# MCUPro.net
KiCad netlist of a schematic drawn in Altium Designer
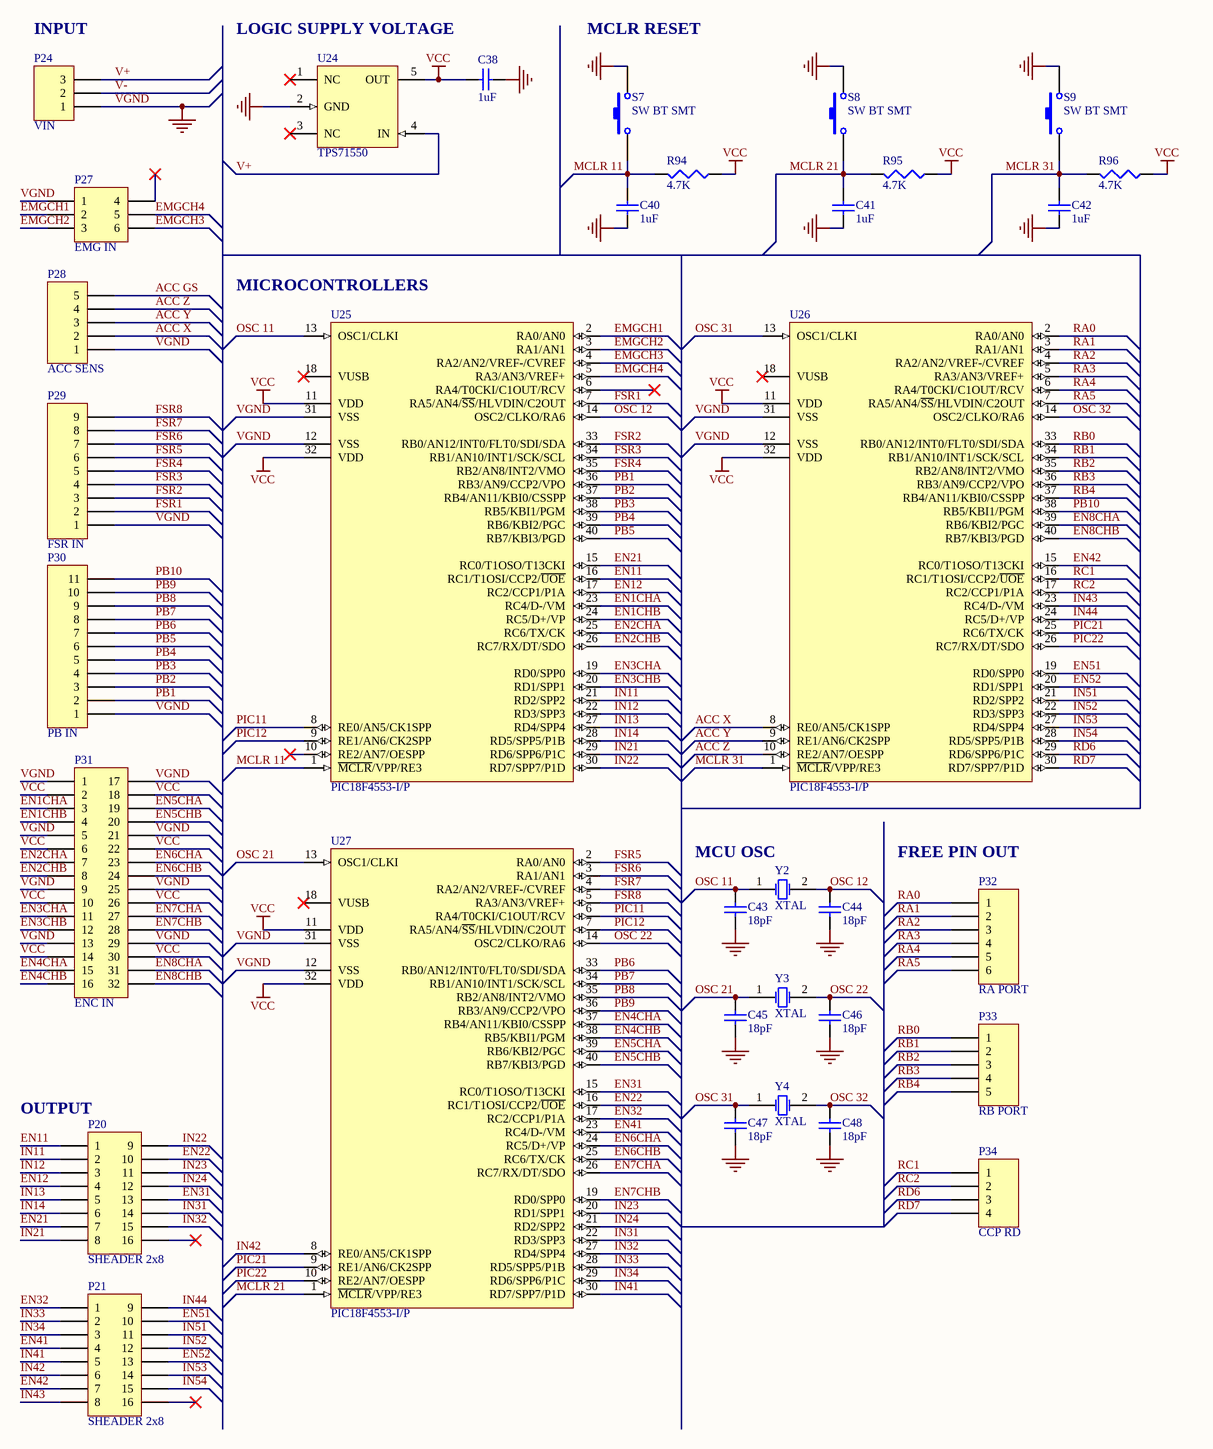
[diagram p0: MCUPro.SchDoc]

(export (version "E")
  (design (tool "Eeschema 10.0.6"))
  (components
    (comp (ref "C38")
      (value "1uF")
      (footprint "CAPC2012M")
      (description "Capacitor (Semiconductor SIM Model)")
      (fields (field (name "Comment") "Cap Semi") (field (name "PUBLISHER") "Altium Limited"))
      (libsource (lib "Miscellaneous Devices") (part "Cap Semi"))
    )
    (comp (ref "C40")
      (value "1uF")
      (footprint "CAPC2012M")
      (description "Capacitor (Semiconductor SIM Model)")
      (fields (field (name "Comment") "Cap Semi") (field (name "PUBLISHER") "Altium Limited"))
      (libsource (lib "Miscellaneous Devices") (part "Cap Semi"))
    )
    (comp (ref "C41")
      (value "1uF")
      (footprint "CAPC2012M")
      (description "Capacitor (Semiconductor SIM Model)")
      (fields (field (name "Comment") "Cap Semi") (field (name "PUBLISHER") "Altium Limited"))
      (libsource (lib "Miscellaneous Devices") (part "Cap Semi"))
    )
    (comp (ref "C42")
      (value "1uF")
      (footprint "CAPC2012M")
      (description "Capacitor (Semiconductor SIM Model)")
      (fields (field (name "Comment") "Cap Semi") (field (name "PUBLISHER") "Altium Limited"))
      (libsource (lib "Miscellaneous Devices") (part "Cap Semi"))
    )
    (comp (ref "C43")
      (value "18pF")
      (footprint "C1206")
      (description "Capacitor (Semiconductor SIM Model)")
      (fields (field (name "Comment") "Cap Semi") (field (name "PUBLISHER") "Altium Limited"))
      (libsource (lib "Miscellaneous Devices") (part "Cap Semi"))
    )
    (comp (ref "C44")
      (value "18pF")
      (footprint "C1206")
      (description "Capacitor (Semiconductor SIM Model)")
      (fields (field (name "Comment") "Cap Semi") (field (name "PUBLISHER") "Altium Limited"))
      (libsource (lib "Miscellaneous Devices") (part "Cap Semi"))
    )
    (comp (ref "C45")
      (value "18pF")
      (footprint "C1206")
      (description "Capacitor (Semiconductor SIM Model)")
      (fields (field (name "Comment") "Cap Semi") (field (name "PUBLISHER") "Altium Limited"))
      (libsource (lib "Miscellaneous Devices") (part "Cap Semi"))
    )
    (comp (ref "C46")
      (value "18pF")
      (footprint "C1206")
      (description "Capacitor (Semiconductor SIM Model)")
      (fields (field (name "Comment") "Cap Semi") (field (name "PUBLISHER") "Altium Limited"))
      (libsource (lib "Miscellaneous Devices") (part "Cap Semi"))
    )
    (comp (ref "C47")
      (value "18pF")
      (footprint "C1206")
      (description "Capacitor (Semiconductor SIM Model)")
      (fields (field (name "Comment") "Cap Semi") (field (name "PUBLISHER") "Altium Limited"))
      (libsource (lib "Miscellaneous Devices") (part "Cap Semi"))
    )
    (comp (ref "C48")
      (value "18pF")
      (footprint "C1206")
      (description "Capacitor (Semiconductor SIM Model)")
      (fields (field (name "Comment") "Cap Semi") (field (name "PUBLISHER") "Altium Limited"))
      (libsource (lib "Miscellaneous Devices") (part "Cap Semi"))
    )
    (comp (ref "P20")
      (value "SHEADER 2x8")
      (footprint "SHBH 2X8")
      (description "Shrouded Box Header: 2x8-Pin, 0.100\" (2.54 mm) Male")
      (libsource (lib "LitoLibrary") (part "SB Header 2x8"))
    )
    (comp (ref "P21")
      (value "SHEADER 2x8")
      (footprint "SHBH 2X8")
      (description "Shrouded Box Header: 2x8-Pin, 0.100\" (2.54 mm) Male")
      (libsource (lib "LitoLibrary") (part "SB Header 2x8"))
    )
    (comp (ref "P24")
      (value "VIN")
      (footprint "AZUL5-3")
      (description "Header, 3-Pin")
      (fields (field (name "PUBLISHER") "Altium Limited"))
      (libsource (lib "Miscellaneous Connectors") (part "Header 3"))
    )
    (comp (ref "P27")
      (value "EMG IN")
      (footprint "SHBH 2x3")
      (description "Shrouded Box Header: 2x8-Pin, 0.100\" (2.54 mm) Male")
      (libsource (lib "LitoLibrary") (part "SB Header 2x3"))
    )
    (comp (ref "P28")
      (value "ACC SENS")
      (footprint "HDR1X5H")
      (description "Header, 5-Pin, Right Angle")
      (fields (field (name "PUBLISHER") "Altium Limited"))
      (libsource (lib "Miscellaneous Connectors") (part "Header 5H"))
    )
    (comp (ref "P29")
      (value "FSR IN")
      (footprint "HDR1X9H")
      (description "Header, 9-Pin, Right Angle")
      (fields (field (name "PUBLISHER") "Altium Limited"))
      (libsource (lib "Miscellaneous Connectors") (part "Header 9H"))
    )
    (comp (ref "P30")
      (value "PB IN")
      (footprint "HDR1X11H")
      (description "Header, 11-Pin, Right Angle")
      (fields (field (name "PUBLISHER") "Altium Limited"))
      (libsource (lib "Miscellaneous Connectors") (part "Header 11H"))
    )
    (comp (ref "P31")
      (value "ENC IN")
      (footprint "HDR2X16_CEN")
      (description "Header, 16-Pin, Dual row")
      (fields (field (name "PUBLISHER") "Altium Limited"))
      (libsource (lib "Miscellaneous Connectors") (part "Header 16X2A"))
    )
    (comp (ref "P32")
      (value "RA PORT")
      (footprint "AZUL5-6")
      (description "Header, 6-Pin")
      (fields (field (name "PUBLISHER") "Altium Limited"))
      (libsource (lib "Miscellaneous Connectors") (part "Header 6"))
    )
    (comp (ref "P33")
      (value "RB PORT")
      (footprint "HDR1X5")
      (description "Header, 5-Pin")
      (fields (field (name "PUBLISHER") "Altium Limited"))
      (libsource (lib "Miscellaneous Connectors") (part "Header 5"))
    )
    (comp (ref "P34")
      (value "CCP RD")
      (footprint "HDR1X4")
      (description "Header, 4-Pin")
      (fields (field (name "PUBLISHER") "Altium Limited"))
      (libsource (lib "Miscellaneous Connectors") (part "Header 4"))
    )
    (comp (ref "R94")
      (value "4.7K")
      (footprint "RESC3225M")
      (description "Resistor")
      (fields (field (name "Comment") "Res3") (field (name "PUBLISHER") "Altium Limited"))
      (libsource (lib "Miscellaneous Devices") (part "Res3"))
    )
    (comp (ref "R95")
      (value "4.7K")
      (footprint "RESC3225M")
      (description "Resistor")
      (fields (field (name "Comment") "Res3") (field (name "PUBLISHER") "Altium Limited"))
      (libsource (lib "Miscellaneous Devices") (part "Res3"))
    )
    (comp (ref "R96")
      (value "4.7K")
      (footprint "RESC3225M")
      (description "Resistor")
      (fields (field (name "Comment") "Res3") (field (name "PUBLISHER") "Altium Limited"))
      (libsource (lib "Miscellaneous Devices") (part "Res3"))
    )
    (comp (ref "S7")
      (value "SW BT SMT")
      (footprint "PBOTTON SMT4")
      (description "Pushbutton Switches FSM2JSMAASTR=6MM TACT SWITCH,")
      (libsource (lib "LitoLibrary") (part "SW PB 6mm"))
    )
    (comp (ref "S8")
      (value "SW BT SMT")
      (footprint "PBOTTON SMT4")
      (description "Pushbutton Switches FSM2JSMAASTR=6MM TACT SWITCH,")
      (libsource (lib "LitoLibrary") (part "SW PB 6mm"))
    )
    (comp (ref "S9")
      (value "SW BT SMT")
      (footprint "PBOTTON SMT4")
      (description "Pushbutton Switches FSM2JSMAASTR=6MM TACT SWITCH,")
      (libsource (lib "LitoLibrary") (part "SW PB 6mm"))
    )
    (comp (ref "U24")
      (value "TPS71550")
      (footprint "SOT353-5L")
      (libsource (lib "LitoLibrary") (part "TPS71550"))
    )
    (comp (ref "U25")
      (value "PIC18F4553-I/P")
      (footprint "PDIP600-P40")
      (fields (field (name "PUBLISHER") "Altium Limited"))
      (libsource (lib "Microchip Microcontroller 8-Bit PIC18") (part "PIC18F4553-I/P"))
    )
    (comp (ref "U26")
      (value "PIC18F4553-I/P")
      (footprint "PDIP600-P40")
      (fields (field (name "PUBLISHER") "Altium Limited"))
      (libsource (lib "Microchip Microcontroller 8-Bit PIC18") (part "PIC18F4553-I/P"))
    )
    (comp (ref "U27")
      (value "PIC18F4553-I/P")
      (footprint "PDIP600-P40")
      (fields (field (name "PUBLISHER") "Altium Limited"))
      (libsource (lib "Microchip Microcontroller 8-Bit PIC18") (part "PIC18F4553-I/P"))
    )
    (comp (ref "Y2")
      (value "XTAL")
      (footprint "XTAL-1")
      (description "Crystal Oscillator")
      (fields (field (name "PUBLISHER") "Altium Limited"))
      (libsource (lib "Miscellaneous Devices") (part "XTAL"))
    )
    (comp (ref "Y3")
      (value "XTAL")
      (footprint "XTAL-1")
      (description "Crystal Oscillator")
      (fields (field (name "PUBLISHER") "Altium Limited"))
      (libsource (lib "Miscellaneous Devices") (part "XTAL"))
    )
    (comp (ref "Y4")
      (value "XTAL")
      (footprint "XTAL-1")
      (description "Crystal Oscillator")
      (fields (field (name "PUBLISHER") "Altium Limited"))
      (libsource (lib "Miscellaneous Devices") (part "XTAL"))
    )
  )
  (nets
    (net (code "1") (name "/ACC GS") (class "Default")
      (node (ref "P28") (pin "5") (pinfunction "5_5") (pintype "passive"))
    )
    (net (code "2") (name "/ACC X") (class "Default")
      (node (ref "P28") (pin "2") (pinfunction "2_2") (pintype "passive"))
      (node (ref "U26") (pin "8") (pinfunction "RE0/AN5/CK1SPP_8") (pintype "bidirectional"))
    )
    (net (code "3") (name "/ACC Y") (class "Default")
      (node (ref "P28") (pin "3") (pinfunction "3_3") (pintype "passive"))
      (node (ref "U26") (pin "9") (pinfunction "RE1/AN6/CK2SPP_9") (pintype "bidirectional"))
    )
    (net (code "4") (name "/ACC Z") (class "Default")
      (node (ref "P28") (pin "4") (pinfunction "4_4") (pintype "passive"))
      (node (ref "U26") (pin "10") (pinfunction "RE2/AN7/OESPP_10") (pintype "bidirectional"))
    )
    (net (code "5") (name "/EMGCH1") (class "Default")
      (node (ref "P27") (pin "2") (pinfunction "2_2") (pintype "passive"))
      (node (ref "U25") (pin "2") (pinfunction "RA0/AN0_2") (pintype "bidirectional"))
    )
    (net (code "6") (name "/EMGCH2") (class "Default")
      (node (ref "P27") (pin "3") (pinfunction "3_3") (pintype "passive"))
      (node (ref "U25") (pin "3") (pinfunction "RA1/AN1_3") (pintype "bidirectional"))
    )
    (net (code "7") (name "/EMGCH3") (class "Default")
      (node (ref "P27") (pin "6") (pinfunction "6_6") (pintype "passive"))
      (node (ref "U25") (pin "4") (pinfunction "RA2/AN2/VREF-/CVREF_4") (pintype "bidirectional"))
    )
    (net (code "8") (name "/EMGCH4") (class "Default")
      (node (ref "P27") (pin "5") (pinfunction "5_5") (pintype "passive"))
      (node (ref "U25") (pin "5") (pinfunction "RA3/AN3/VREF+_5") (pintype "bidirectional"))
    )
    (net (code "9") (name "/EN1CHA") (class "Default")
      (node (ref "P31") (pin "3") (pinfunction "3_3") (pintype "passive"))
      (node (ref "U25") (pin "23") (pinfunction "RC4/D-/VM_23") (pintype "bidirectional"))
    )
    (net (code "10") (name "/EN1CHB") (class "Default")
      (node (ref "P31") (pin "4") (pinfunction "4_4") (pintype "passive"))
      (node (ref "U25") (pin "24") (pinfunction "RC5/D+/VP_24") (pintype "bidirectional"))
    )
    (net (code "11") (name "/EN2CHA") (class "Default")
      (node (ref "P31") (pin "7") (pinfunction "7_7") (pintype "passive"))
      (node (ref "U25") (pin "25") (pinfunction "RC6/TX/CK_25") (pintype "bidirectional"))
    )
    (net (code "12") (name "/EN2CHB") (class "Default")
      (node (ref "P31") (pin "8") (pinfunction "8_8") (pintype "passive"))
      (node (ref "U25") (pin "26") (pinfunction "RC7/RX/DT/SDO_26") (pintype "bidirectional"))
    )
    (net (code "13") (name "/EN3CHA") (class "Default")
      (node (ref "P31") (pin "11") (pinfunction "11_11") (pintype "passive"))
      (node (ref "U25") (pin "19") (pinfunction "RD0/SPP0_19") (pintype "bidirectional"))
    )
    (net (code "14") (name "/EN3CHB") (class "Default")
      (node (ref "P31") (pin "12") (pinfunction "12_12") (pintype "passive"))
      (node (ref "U25") (pin "20") (pinfunction "RD1/SPP1_20") (pintype "bidirectional"))
    )
    (net (code "15") (name "/EN4CHA") (class "Default")
      (node (ref "P31") (pin "15") (pinfunction "15_15") (pintype "passive"))
      (node (ref "U27") (pin "37") (pinfunction "RB4/AN11/KBI0/CSSPP_37") (pintype "bidirectional"))
    )
    (net (code "16") (name "/EN4CHB") (class "Default")
      (node (ref "P31") (pin "16") (pinfunction "16_16") (pintype "passive"))
      (node (ref "U27") (pin "38") (pinfunction "RB5/KBI1/PGM_38") (pintype "bidirectional"))
    )
    (net (code "17") (name "/EN5CHA") (class "Default")
      (node (ref "P31") (pin "19") (pinfunction "19_19") (pintype "passive"))
      (node (ref "U27") (pin "39") (pinfunction "RB6/KBI2/PGC_39") (pintype "bidirectional"))
    )
    (net (code "18") (name "/EN5CHB") (class "Default")
      (node (ref "P31") (pin "20") (pinfunction "20_20") (pintype "passive"))
      (node (ref "U27") (pin "40") (pinfunction "RB7/KBI3/PGD_40") (pintype "bidirectional"))
    )
    (net (code "19") (name "/EN6CHA") (class "Default")
      (node (ref "P31") (pin "23") (pinfunction "23_23") (pintype "passive"))
      (node (ref "U27") (pin "24") (pinfunction "RC5/D+/VP_24") (pintype "bidirectional"))
    )
    (net (code "20") (name "/EN6CHB") (class "Default")
      (node (ref "P31") (pin "24") (pinfunction "24_24") (pintype "passive"))
      (node (ref "U27") (pin "25") (pinfunction "RC6/TX/CK_25") (pintype "bidirectional"))
    )
    (net (code "21") (name "/EN7CHA") (class "Default")
      (node (ref "P31") (pin "27") (pinfunction "27_27") (pintype "passive"))
      (node (ref "U27") (pin "26") (pinfunction "RC7/RX/DT/SDO_26") (pintype "bidirectional"))
    )
    (net (code "22") (name "/EN7CHB") (class "Default")
      (node (ref "P31") (pin "28") (pinfunction "28_28") (pintype "passive"))
      (node (ref "U27") (pin "19") (pinfunction "RD0/SPP0_19") (pintype "bidirectional"))
    )
    (net (code "23") (name "/EN8CHA") (class "Default")
      (node (ref "P31") (pin "31") (pinfunction "31_31") (pintype "passive"))
      (node (ref "U26") (pin "39") (pinfunction "RB6/KBI2/PGC_39") (pintype "bidirectional"))
    )
    (net (code "24") (name "/EN8CHB") (class "Default")
      (node (ref "P31") (pin "32") (pinfunction "32_32") (pintype "passive"))
      (node (ref "U26") (pin "40") (pinfunction "RB7/KBI3/PGD_40") (pintype "bidirectional"))
    )
    (net (code "25") (name "/EN11") (class "Default")
      (node (ref "P20") (pin "1") (pinfunction "1_1") (pintype "passive"))
      (node (ref "U25") (pin "16") (pinfunction "RC1/T1OSI/CCP2/~{UOE}_16") (pintype "bidirectional"))
    )
    (net (code "26") (name "/EN12") (class "Default")
      (node (ref "P20") (pin "4") (pinfunction "4_4") (pintype "passive"))
      (node (ref "U25") (pin "17") (pinfunction "RC2/CCP1/P1A_17") (pintype "bidirectional"))
    )
    (net (code "27") (name "/EN21") (class "Default")
      (node (ref "P20") (pin "7") (pinfunction "7_7") (pintype "passive"))
      (node (ref "U25") (pin "15") (pinfunction "RC0/T1OSO/T13CKI_15") (pintype "bidirectional"))
    )
    (net (code "28") (name "/EN22") (class "Default")
      (node (ref "P20") (pin "10") (pinfunction "10_10") (pintype "passive"))
      (node (ref "U27") (pin "16") (pinfunction "RC1/T1OSI/CCP2/~{UOE}_16") (pintype "bidirectional"))
    )
    (net (code "29") (name "/EN31") (class "Default")
      (node (ref "P20") (pin "13") (pinfunction "13_13") (pintype "passive"))
      (node (ref "U27") (pin "15") (pinfunction "RC0/T1OSO/T13CKI_15") (pintype "bidirectional"))
    )
    (net (code "30") (name "/EN32") (class "Default")
      (node (ref "P21") (pin "1") (pinfunction "1_1") (pintype "passive"))
      (node (ref "U27") (pin "17") (pinfunction "RC2/CCP1/P1A_17") (pintype "bidirectional"))
    )
    (net (code "31") (name "/EN41") (class "Default")
      (node (ref "P21") (pin "4") (pinfunction "4_4") (pintype "passive"))
      (node (ref "U27") (pin "23") (pinfunction "RC4/D-/VM_23") (pintype "bidirectional"))
    )
    (net (code "32") (name "/EN42") (class "Default")
      (node (ref "P21") (pin "7") (pinfunction "7_7") (pintype "passive"))
      (node (ref "U26") (pin "15") (pinfunction "RC0/T1OSO/T13CKI_15") (pintype "bidirectional"))
    )
    (net (code "33") (name "/EN51") (class "Default")
      (node (ref "P21") (pin "10") (pinfunction "10_10") (pintype "passive"))
      (node (ref "U26") (pin "19") (pinfunction "RD0/SPP0_19") (pintype "bidirectional"))
    )
    (net (code "34") (name "/EN52") (class "Default")
      (node (ref "P21") (pin "13") (pinfunction "13_13") (pintype "passive"))
      (node (ref "U26") (pin "20") (pinfunction "RD1/SPP1_20") (pintype "bidirectional"))
    )
    (net (code "35") (name "/FSR1") (class "Default")
      (node (ref "P29") (pin "2") (pinfunction "2_2") (pintype "passive"))
      (node (ref "U25") (pin "7") (pinfunction "RA5/AN4/~{SS}/HLVDIN/C2OUT_7") (pintype "bidirectional"))
    )
    (net (code "36") (name "/FSR2") (class "Default")
      (node (ref "P29") (pin "3") (pinfunction "3_3") (pintype "passive"))
      (node (ref "U25") (pin "33") (pinfunction "RB0/AN12/INT0/FLT0/SDI/SDA_33") (pintype "bidirectional"))
    )
    (net (code "37") (name "/FSR3") (class "Default")
      (node (ref "P29") (pin "4") (pinfunction "4_4") (pintype "passive"))
      (node (ref "U25") (pin "34") (pinfunction "RB1/AN10/INT1/SCK/SCL_34") (pintype "bidirectional"))
    )
    (net (code "38") (name "/FSR4") (class "Default")
      (node (ref "P29") (pin "5") (pinfunction "5_5") (pintype "passive"))
      (node (ref "U25") (pin "35") (pinfunction "RB2/AN8/INT2/VMO_35") (pintype "bidirectional"))
    )
    (net (code "39") (name "/FSR5") (class "Default")
      (node (ref "P29") (pin "6") (pinfunction "6_6") (pintype "passive"))
      (node (ref "U27") (pin "2") (pinfunction "RA0/AN0_2") (pintype "bidirectional"))
    )
    (net (code "40") (name "/FSR6") (class "Default")
      (node (ref "P29") (pin "7") (pinfunction "7_7") (pintype "passive"))
      (node (ref "U27") (pin "3") (pinfunction "RA1/AN1_3") (pintype "bidirectional"))
    )
    (net (code "41") (name "/FSR7") (class "Default")
      (node (ref "P29") (pin "8") (pinfunction "8_8") (pintype "passive"))
      (node (ref "U27") (pin "4") (pinfunction "RA2/AN2/VREF-/CVREF_4") (pintype "bidirectional"))
    )
    (net (code "42") (name "/FSR8") (class "Default")
      (node (ref "P29") (pin "9") (pinfunction "9_9") (pintype "passive"))
      (node (ref "U27") (pin "5") (pinfunction "RA3/AN3/VREF+_5") (pintype "bidirectional"))
    )
    (net (code "43") (name "/IN11") (class "Default")
      (node (ref "P20") (pin "2") (pinfunction "2_2") (pintype "passive"))
      (node (ref "U25") (pin "21") (pinfunction "RD2/SPP2_21") (pintype "bidirectional"))
    )
    (net (code "44") (name "/IN12") (class "Default")
      (node (ref "P20") (pin "3") (pinfunction "3_3") (pintype "passive"))
      (node (ref "U25") (pin "22") (pinfunction "RD3/SPP3_22") (pintype "bidirectional"))
    )
    (net (code "45") (name "/IN13") (class "Default")
      (node (ref "P20") (pin "5") (pinfunction "5_5") (pintype "passive"))
      (node (ref "U25") (pin "27") (pinfunction "RD4/SPP4_27") (pintype "bidirectional"))
    )
    (net (code "46") (name "/IN14") (class "Default")
      (node (ref "P20") (pin "6") (pinfunction "6_6") (pintype "passive"))
      (node (ref "U25") (pin "28") (pinfunction "RD5/SPP5/P1B_28") (pintype "bidirectional"))
    )
    (net (code "47") (name "/IN21") (class "Default")
      (node (ref "P20") (pin "8") (pinfunction "8_8") (pintype "passive"))
      (node (ref "U25") (pin "29") (pinfunction "RD6/SPP6/P1C_29") (pintype "bidirectional"))
    )
    (net (code "48") (name "/IN22") (class "Default")
      (node (ref "P20") (pin "9") (pinfunction "9_9") (pintype "passive"))
      (node (ref "U25") (pin "30") (pinfunction "RD7/SPP7/P1D_30") (pintype "bidirectional"))
    )
    (net (code "49") (name "/IN23") (class "Default")
      (node (ref "P20") (pin "11") (pinfunction "11_11") (pintype "passive"))
      (node (ref "U27") (pin "20") (pinfunction "RD1/SPP1_20") (pintype "bidirectional"))
    )
    (net (code "50") (name "/IN24") (class "Default")
      (node (ref "P20") (pin "12") (pinfunction "12_12") (pintype "passive"))
      (node (ref "U27") (pin "21") (pinfunction "RD2/SPP2_21") (pintype "bidirectional"))
    )
    (net (code "51") (name "/IN31") (class "Default")
      (node (ref "P20") (pin "14") (pinfunction "14_14") (pintype "passive"))
      (node (ref "U27") (pin "22") (pinfunction "RD3/SPP3_22") (pintype "bidirectional"))
    )
    (net (code "52") (name "/IN32") (class "Default")
      (node (ref "P20") (pin "15") (pinfunction "15_15") (pintype "passive"))
      (node (ref "U27") (pin "27") (pinfunction "RD4/SPP4_27") (pintype "bidirectional"))
    )
    (net (code "53") (name "/IN33") (class "Default")
      (node (ref "P21") (pin "2") (pinfunction "2_2") (pintype "passive"))
      (node (ref "U27") (pin "28") (pinfunction "RD5/SPP5/P1B_28") (pintype "bidirectional"))
    )
    (net (code "54") (name "/IN34") (class "Default")
      (node (ref "P21") (pin "3") (pinfunction "3_3") (pintype "passive"))
      (node (ref "U27") (pin "29") (pinfunction "RD6/SPP6/P1C_29") (pintype "bidirectional"))
    )
    (net (code "55") (name "/IN41") (class "Default")
      (node (ref "P21") (pin "5") (pinfunction "5_5") (pintype "passive"))
      (node (ref "U27") (pin "30") (pinfunction "RD7/SPP7/P1D_30") (pintype "bidirectional"))
    )
    (net (code "56") (name "/IN42") (class "Default")
      (node (ref "P21") (pin "6") (pinfunction "6_6") (pintype "passive"))
      (node (ref "U27") (pin "8") (pinfunction "RE0/AN5/CK1SPP_8") (pintype "bidirectional"))
    )
    (net (code "57") (name "/IN43") (class "Default")
      (node (ref "P21") (pin "8") (pinfunction "8_8") (pintype "passive"))
      (node (ref "U26") (pin "23") (pinfunction "RC4/D-/VM_23") (pintype "bidirectional"))
    )
    (net (code "58") (name "/IN44") (class "Default")
      (node (ref "P21") (pin "9") (pinfunction "9_9") (pintype "passive"))
      (node (ref "U26") (pin "24") (pinfunction "RC5/D+/VP_24") (pintype "bidirectional"))
    )
    (net (code "59") (name "/IN51") (class "Default")
      (node (ref "P21") (pin "11") (pinfunction "11_11") (pintype "passive"))
      (node (ref "U26") (pin "21") (pinfunction "RD2/SPP2_21") (pintype "bidirectional"))
    )
    (net (code "60") (name "/IN52") (class "Default")
      (node (ref "P21") (pin "12") (pinfunction "12_12") (pintype "passive"))
      (node (ref "U26") (pin "22") (pinfunction "RD3/SPP3_22") (pintype "bidirectional"))
    )
    (net (code "61") (name "/IN53") (class "Default")
      (node (ref "P21") (pin "14") (pinfunction "14_14") (pintype "passive"))
      (node (ref "U26") (pin "27") (pinfunction "RD4/SPP4_27") (pintype "bidirectional"))
    )
    (net (code "62") (name "/IN54") (class "Default")
      (node (ref "P21") (pin "15") (pinfunction "15_15") (pintype "passive"))
      (node (ref "U26") (pin "28") (pinfunction "RD5/SPP5/P1B_28") (pintype "bidirectional"))
    )
    (net (code "63") (name "/MCLR 11") (class "Default")
      (node (ref "C40") (pin "1") (pinfunction "1_1") (pintype "passive"))
      (node (ref "R94") (pin "2") (pinfunction "2_2") (pintype "passive"))
      (node (ref "S7") (pin "1") (pinfunction "1_1") (pintype "passive"))
      (node (ref "U25") (pin "1") (pinfunction "~{MCLR}/VPP/RE3_1") (pintype "input"))
    )
    (net (code "64") (name "/MCLR 21") (class "Default")
      (node (ref "C41") (pin "1") (pinfunction "1_1") (pintype "passive"))
      (node (ref "R95") (pin "2") (pinfunction "2_2") (pintype "passive"))
      (node (ref "S8") (pin "1") (pinfunction "1_1") (pintype "passive"))
      (node (ref "U27") (pin "1") (pinfunction "~{MCLR}/VPP/RE3_1") (pintype "input"))
    )
    (net (code "65") (name "/MCLR 31") (class "Default")
      (node (ref "C42") (pin "1") (pinfunction "1_1") (pintype "passive"))
      (node (ref "R96") (pin "2") (pinfunction "2_2") (pintype "passive"))
      (node (ref "S9") (pin "1") (pinfunction "1_1") (pintype "passive"))
      (node (ref "U26") (pin "1") (pinfunction "~{MCLR}/VPP/RE3_1") (pintype "input"))
    )
    (net (code "66") (name "/OSC 11") (class "Default")
      (node (ref "C43") (pin "1") (pinfunction "1_1") (pintype "passive"))
      (node (ref "U25") (pin "13") (pinfunction "OSC1/CLKI_13") (pintype "input"))
      (node (ref "Y2") (pin "1") (pinfunction "OSC1_1") (pintype "passive"))
    )
    (net (code "67") (name "/OSC 12") (class "Default")
      (node (ref "C44") (pin "1") (pinfunction "1_1") (pintype "passive"))
      (node (ref "U25") (pin "14") (pinfunction "OSC2/CLKO/RA6_14") (pintype "bidirectional"))
      (node (ref "Y2") (pin "2") (pinfunction "OSC2_2") (pintype "passive"))
    )
    (net (code "68") (name "/OSC 21") (class "Default")
      (node (ref "C45") (pin "1") (pinfunction "1_1") (pintype "passive"))
      (node (ref "U27") (pin "13") (pinfunction "OSC1/CLKI_13") (pintype "input"))
      (node (ref "Y3") (pin "1") (pinfunction "OSC1_1") (pintype "passive"))
    )
    (net (code "69") (name "/OSC 22") (class "Default")
      (node (ref "C46") (pin "1") (pinfunction "1_1") (pintype "passive"))
      (node (ref "U27") (pin "14") (pinfunction "OSC2/CLKO/RA6_14") (pintype "bidirectional"))
      (node (ref "Y3") (pin "2") (pinfunction "OSC2_2") (pintype "passive"))
    )
    (net (code "70") (name "/OSC 31") (class "Default")
      (node (ref "C47") (pin "1") (pinfunction "1_1") (pintype "passive"))
      (node (ref "U26") (pin "13") (pinfunction "OSC1/CLKI_13") (pintype "input"))
      (node (ref "Y4") (pin "1") (pinfunction "OSC1_1") (pintype "passive"))
    )
    (net (code "71") (name "/OSC 32") (class "Default")
      (node (ref "C48") (pin "1") (pinfunction "1_1") (pintype "passive"))
      (node (ref "U26") (pin "14") (pinfunction "OSC2/CLKO/RA6_14") (pintype "bidirectional"))
      (node (ref "Y4") (pin "2") (pinfunction "OSC2_2") (pintype "passive"))
    )
    (net (code "72") (name "/PB1") (class "Default")
      (node (ref "P30") (pin "2") (pinfunction "2_2") (pintype "passive"))
      (node (ref "U25") (pin "36") (pinfunction "RB3/AN9/CCP2/VPO_36") (pintype "bidirectional"))
    )
    (net (code "73") (name "/PB2") (class "Default")
      (node (ref "P30") (pin "3") (pinfunction "3_3") (pintype "passive"))
      (node (ref "U25") (pin "37") (pinfunction "RB4/AN11/KBI0/CSSPP_37") (pintype "bidirectional"))
    )
    (net (code "74") (name "/PB3") (class "Default")
      (node (ref "P30") (pin "4") (pinfunction "4_4") (pintype "passive"))
      (node (ref "U25") (pin "38") (pinfunction "RB5/KBI1/PGM_38") (pintype "bidirectional"))
    )
    (net (code "75") (name "/PB4") (class "Default")
      (node (ref "P30") (pin "5") (pinfunction "5_5") (pintype "passive"))
      (node (ref "U25") (pin "39") (pinfunction "RB6/KBI2/PGC_39") (pintype "bidirectional"))
    )
    (net (code "76") (name "/PB5") (class "Default")
      (node (ref "P30") (pin "6") (pinfunction "6_6") (pintype "passive"))
      (node (ref "U25") (pin "40") (pinfunction "RB7/KBI3/PGD_40") (pintype "bidirectional"))
    )
    (net (code "77") (name "/PB6") (class "Default")
      (node (ref "P30") (pin "7") (pinfunction "7_7") (pintype "passive"))
      (node (ref "U27") (pin "33") (pinfunction "RB0/AN12/INT0/FLT0/SDI/SDA_33") (pintype "bidirectional"))
    )
    (net (code "78") (name "/PB7") (class "Default")
      (node (ref "P30") (pin "8") (pinfunction "8_8") (pintype "passive"))
      (node (ref "U27") (pin "34") (pinfunction "RB1/AN10/INT1/SCK/SCL_34") (pintype "bidirectional"))
    )
    (net (code "79") (name "/PB8") (class "Default")
      (node (ref "P30") (pin "9") (pinfunction "9_9") (pintype "passive"))
      (node (ref "U27") (pin "35") (pinfunction "RB2/AN8/INT2/VMO_35") (pintype "bidirectional"))
    )
    (net (code "80") (name "/PB9") (class "Default")
      (node (ref "P30") (pin "10") (pinfunction "10_10") (pintype "passive"))
      (node (ref "U27") (pin "36") (pinfunction "RB3/AN9/CCP2/VPO_36") (pintype "bidirectional"))
    )
    (net (code "81") (name "/PB10") (class "Default")
      (node (ref "P30") (pin "11") (pinfunction "11_11") (pintype "passive"))
      (node (ref "U26") (pin "38") (pinfunction "RB5/KBI1/PGM_38") (pintype "bidirectional"))
    )
    (net (code "82") (name "/PIC11") (class "Default")
      (node (ref "U25") (pin "8") (pinfunction "RE0/AN5/CK1SPP_8") (pintype "bidirectional"))
      (node (ref "U27") (pin "6") (pinfunction "RA4/T0CKI/C1OUT/RCV_6") (pintype "bidirectional"))
    )
    (net (code "83") (name "/PIC12") (class "Default")
      (node (ref "U25") (pin "9") (pinfunction "RE1/AN6/CK2SPP_9") (pintype "bidirectional"))
      (node (ref "U27") (pin "7") (pinfunction "RA5/AN4/~{SS}/HLVDIN/C2OUT_7") (pintype "bidirectional"))
    )
    (net (code "84") (name "/PIC21") (class "Default")
      (node (ref "U26") (pin "25") (pinfunction "RC6/TX/CK_25") (pintype "bidirectional"))
      (node (ref "U27") (pin "9") (pinfunction "RE1/AN6/CK2SPP_9") (pintype "bidirectional"))
    )
    (net (code "85") (name "/PIC22") (class "Default")
      (node (ref "U26") (pin "26") (pinfunction "RC7/RX/DT/SDO_26") (pintype "bidirectional"))
      (node (ref "U27") (pin "10") (pinfunction "RE2/AN7/OESPP_10") (pintype "bidirectional"))
    )
    (net (code "86") (name "/RA0") (class "Default")
      (node (ref "P32") (pin "1") (pinfunction "1_1") (pintype "passive"))
      (node (ref "U26") (pin "2") (pinfunction "RA0/AN0_2") (pintype "bidirectional"))
    )
    (net (code "87") (name "/RA1") (class "Default")
      (node (ref "P32") (pin "2") (pinfunction "2_2") (pintype "passive"))
      (node (ref "U26") (pin "3") (pinfunction "RA1/AN1_3") (pintype "bidirectional"))
    )
    (net (code "88") (name "/RA2") (class "Default")
      (node (ref "P32") (pin "3") (pinfunction "3_3") (pintype "passive"))
      (node (ref "U26") (pin "4") (pinfunction "RA2/AN2/VREF-/CVREF_4") (pintype "bidirectional"))
    )
    (net (code "89") (name "/RA3") (class "Default")
      (node (ref "P32") (pin "4") (pinfunction "4_4") (pintype "passive"))
      (node (ref "U26") (pin "5") (pinfunction "RA3/AN3/VREF+_5") (pintype "bidirectional"))
    )
    (net (code "90") (name "/RA4") (class "Default")
      (node (ref "P32") (pin "5") (pinfunction "5_5") (pintype "passive"))
      (node (ref "U26") (pin "6") (pinfunction "RA4/T0CKI/C1OUT/RCV_6") (pintype "bidirectional"))
    )
    (net (code "91") (name "/RA5") (class "Default")
      (node (ref "P32") (pin "6") (pinfunction "6_6") (pintype "passive"))
      (node (ref "U26") (pin "7") (pinfunction "RA5/AN4/~{SS}/HLVDIN/C2OUT_7") (pintype "bidirectional"))
    )
    (net (code "92") (name "/RB0") (class "Default")
      (node (ref "P33") (pin "1") (pinfunction "1_1") (pintype "passive"))
      (node (ref "U26") (pin "33") (pinfunction "RB0/AN12/INT0/FLT0/SDI/SDA_33") (pintype "bidirectional"))
    )
    (net (code "93") (name "/RB1") (class "Default")
      (node (ref "P33") (pin "2") (pinfunction "2_2") (pintype "passive"))
      (node (ref "U26") (pin "34") (pinfunction "RB1/AN10/INT1/SCK/SCL_34") (pintype "bidirectional"))
    )
    (net (code "94") (name "/RB2") (class "Default")
      (node (ref "P33") (pin "3") (pinfunction "3_3") (pintype "passive"))
      (node (ref "U26") (pin "35") (pinfunction "RB2/AN8/INT2/VMO_35") (pintype "bidirectional"))
    )
    (net (code "95") (name "/RB3") (class "Default")
      (node (ref "P33") (pin "4") (pinfunction "4_4") (pintype "passive"))
      (node (ref "U26") (pin "36") (pinfunction "RB3/AN9/CCP2/VPO_36") (pintype "bidirectional"))
    )
    (net (code "96") (name "/RB4") (class "Default")
      (node (ref "P33") (pin "5") (pinfunction "5_5") (pintype "passive"))
      (node (ref "U26") (pin "37") (pinfunction "RB4/AN11/KBI0/CSSPP_37") (pintype "bidirectional"))
    )
    (net (code "97") (name "/RC1") (class "Default")
      (node (ref "P34") (pin "1") (pinfunction "1_1") (pintype "passive"))
      (node (ref "U26") (pin "16") (pinfunction "RC1/T1OSI/CCP2/~{UOE}_16") (pintype "bidirectional"))
    )
    (net (code "98") (name "/RC2") (class "Default")
      (node (ref "P34") (pin "2") (pinfunction "2_2") (pintype "passive"))
      (node (ref "U26") (pin "17") (pinfunction "RC2/CCP1/P1A_17") (pintype "bidirectional"))
    )
    (net (code "99") (name "/RD6") (class "Default")
      (node (ref "P34") (pin "3") (pinfunction "3_3") (pintype "passive"))
      (node (ref "U26") (pin "29") (pinfunction "RD6/SPP6/P1C_29") (pintype "bidirectional"))
    )
    (net (code "100") (name "/RD7") (class "Default")
      (node (ref "P34") (pin "4") (pinfunction "4_4") (pintype "passive"))
      (node (ref "U26") (pin "30") (pinfunction "RD7/SPP7/P1D_30") (pintype "bidirectional"))
    )
    (net (code "101") (name "/V+") (class "Default")
      (node (ref "P24") (pin "3") (pinfunction "3_3") (pintype "passive"))
      (node (ref "U24") (pin "4") (pinfunction "IN_4") (pintype "input"))
    )
    (net (code "102") (name "/V-") (class "Default")
      (node (ref "P24") (pin "2") (pinfunction "2_2") (pintype "passive"))
    )
    (net (code "103") (name "GND") (class "Default")
      (node (ref "C38") (pin "2") (pinfunction "2_2") (pintype "passive"))
      (node (ref "C40") (pin "2") (pinfunction "2_2") (pintype "passive"))
      (node (ref "C41") (pin "2") (pinfunction "2_2") (pintype "passive"))
      (node (ref "C42") (pin "2") (pinfunction "2_2") (pintype "passive"))
      (node (ref "C43") (pin "2") (pinfunction "2_2") (pintype "passive"))
      (node (ref "C44") (pin "2") (pinfunction "2_2") (pintype "passive"))
      (node (ref "C45") (pin "2") (pinfunction "2_2") (pintype "passive"))
      (node (ref "C46") (pin "2") (pinfunction "2_2") (pintype "passive"))
      (node (ref "C47") (pin "2") (pinfunction "2_2") (pintype "passive"))
      (node (ref "C48") (pin "2") (pinfunction "2_2") (pintype "passive"))
      (node (ref "P24") (pin "1") (pinfunction "1_1") (pintype "passive"))
      (node (ref "P27") (pin "1") (pinfunction "1_1") (pintype "passive"))
      (node (ref "P28") (pin "1") (pinfunction "1_1") (pintype "passive"))
      (node (ref "P29") (pin "1") (pinfunction "1_1") (pintype "passive"))
      (node (ref "P30") (pin "1") (pinfunction "1_1") (pintype "passive"))
      (node (ref "P31") (pin "1") (pinfunction "1_1") (pintype "passive"))
      (node (ref "P31") (pin "13") (pinfunction "13_13") (pintype "passive"))
      (node (ref "P31") (pin "17") (pinfunction "17_17") (pintype "passive"))
      (node (ref "P31") (pin "21") (pinfunction "21_21") (pintype "passive"))
      (node (ref "P31") (pin "25") (pinfunction "25_25") (pintype "passive"))
      (node (ref "P31") (pin "29") (pinfunction "29_29") (pintype "passive"))
      (node (ref "P31") (pin "5") (pinfunction "5_5") (pintype "passive"))
      (node (ref "P31") (pin "9") (pinfunction "9_9") (pintype "passive"))
      (node (ref "S7") (pin "2") (pinfunction "2_2") (pintype "passive"))
      (node (ref "S8") (pin "2") (pinfunction "2_2") (pintype "passive"))
      (node (ref "S9") (pin "2") (pinfunction "2_2") (pintype "passive"))
      (node (ref "U24") (pin "2") (pinfunction "GND_2") (pintype "input"))
      (node (ref "U25") (pin "12") (pinfunction "VSS_12") (pintype "power_in"))
      (node (ref "U25") (pin "31") (pinfunction "VSS_31") (pintype "power_in"))
      (node (ref "U26") (pin "12") (pinfunction "VSS_12") (pintype "power_in"))
      (node (ref "U26") (pin "31") (pinfunction "VSS_31") (pintype "power_in"))
      (node (ref "U27") (pin "12") (pinfunction "VSS_12") (pintype "power_in"))
      (node (ref "U27") (pin "31") (pinfunction "VSS_31") (pintype "power_in"))
    )
    (net (code "104") (name "VCC") (class "Default")
      (node (ref "C38") (pin "1") (pinfunction "1_1") (pintype "passive"))
      (node (ref "P31") (pin "10") (pinfunction "10_10") (pintype "passive"))
      (node (ref "P31") (pin "14") (pinfunction "14_14") (pintype "passive"))
      (node (ref "P31") (pin "18") (pinfunction "18_18") (pintype "passive"))
      (node (ref "P31") (pin "2") (pinfunction "2_2") (pintype "passive"))
      (node (ref "P31") (pin "22") (pinfunction "22_22") (pintype "passive"))
      (node (ref "P31") (pin "26") (pinfunction "26_26") (pintype "passive"))
      (node (ref "P31") (pin "30") (pinfunction "30_30") (pintype "passive"))
      (node (ref "P31") (pin "6") (pinfunction "6_6") (pintype "passive"))
      (node (ref "R94") (pin "1") (pinfunction "1_1") (pintype "passive"))
      (node (ref "R95") (pin "1") (pinfunction "1_1") (pintype "passive"))
      (node (ref "R96") (pin "1") (pinfunction "1_1") (pintype "passive"))
      (node (ref "U24") (pin "5") (pinfunction "OUT_5") (pintype "passive"))
      (node (ref "U25") (pin "11") (pinfunction "VDD_11") (pintype "power_in"))
      (node (ref "U25") (pin "32") (pinfunction "VDD_32") (pintype "power_in"))
      (node (ref "U26") (pin "11") (pinfunction "VDD_11") (pintype "power_in"))
      (node (ref "U26") (pin "32") (pinfunction "VDD_32") (pintype "power_in"))
      (node (ref "U27") (pin "11") (pinfunction "VDD_11") (pintype "power_in"))
      (node (ref "U27") (pin "32") (pinfunction "VDD_32") (pintype "power_in"))
    )
    (net (code "105") (name "unconnected-(P20-Pad16)") (class "Default")
      (node (ref "P20") (pin "16") (pinfunction "16_16") (pintype "passive+no_connect"))
    )
    (net (code "106") (name "unconnected-(P21-Pad16)") (class "Default")
      (node (ref "P21") (pin "16") (pinfunction "16_16") (pintype "passive+no_connect"))
    )
    (net (code "107") (name "unconnected-(P27-Pad4)") (class "Default")
      (node (ref "P27") (pin "4") (pinfunction "4_4") (pintype "passive+no_connect"))
    )
    (net (code "108") (name "unconnected-(U24-NC-Pad1)") (class "Default")
      (node (ref "U24") (pin "1") (pinfunction "NC_1") (pintype "passive+no_connect"))
    )
    (net (code "109") (name "unconnected-(U24-NC-Pad3)") (class "Default")
      (node (ref "U24") (pin "3") (pinfunction "NC_3") (pintype "passive+no_connect"))
    )
    (net (code "110") (name "unconnected-(U25-RA4{slash}T0CKI{slash}C1OUT{slash}RCV-Pad6)") (class "Default")
      (node (ref "U25") (pin "6") (pinfunction "RA4/T0CKI/C1OUT/RCV_6") (pintype "bidirectional+no_connect"))
    )
    (net (code "111") (name "unconnected-(U25-RE2{slash}AN7{slash}OESPP-Pad10)") (class "Default")
      (node (ref "U25") (pin "10") (pinfunction "RE2/AN7/OESPP_10") (pintype "bidirectional+no_connect"))
    )
    (net (code "112") (name "unconnected-(U25-VUSB-Pad18)") (class "Default")
      (node (ref "U25") (pin "18") (pinfunction "VUSB_18") (pintype "power_in+no_connect"))
    )
    (net (code "113") (name "unconnected-(U26-VUSB-Pad18)") (class "Default")
      (node (ref "U26") (pin "18") (pinfunction "VUSB_18") (pintype "power_in+no_connect"))
    )
    (net (code "114") (name "unconnected-(U27-VUSB-Pad18)") (class "Default")
      (node (ref "U27") (pin "18") (pinfunction "VUSB_18") (pintype "power_in+no_connect"))
    )
  )
)
